# ESP32_with_USBC.net
KiCad netlist of a schematic drawn in Altium Designer
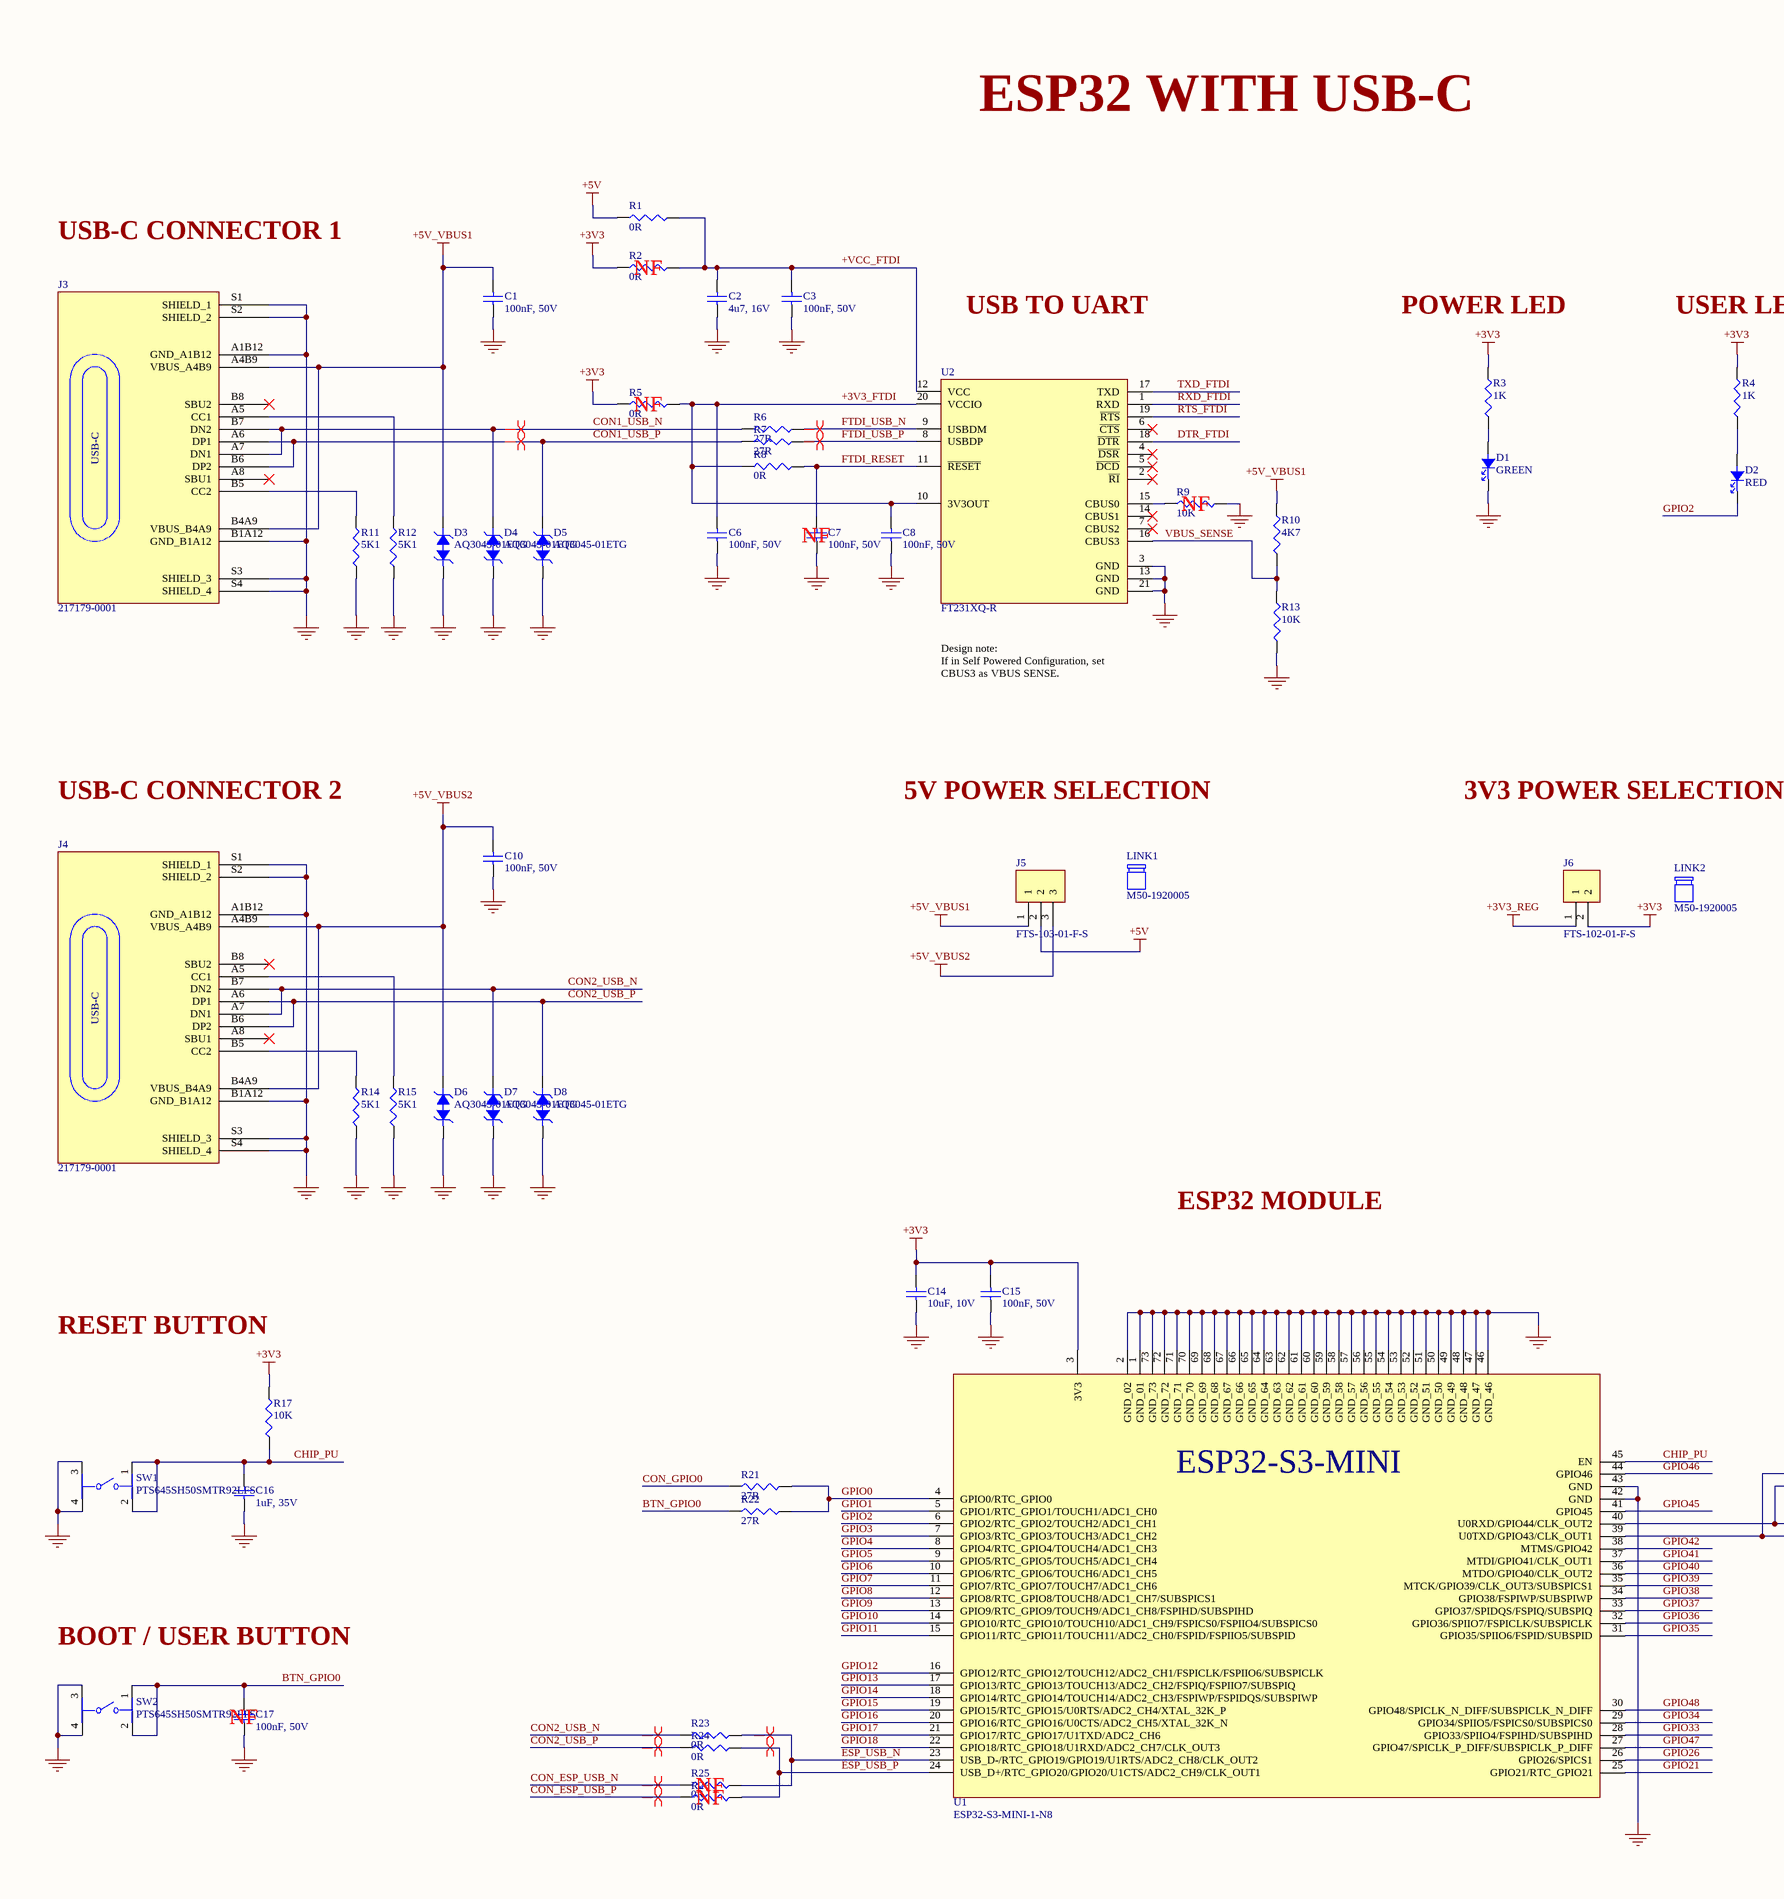
[diagram p0: ESP32 with USBC.SchDoc, left]
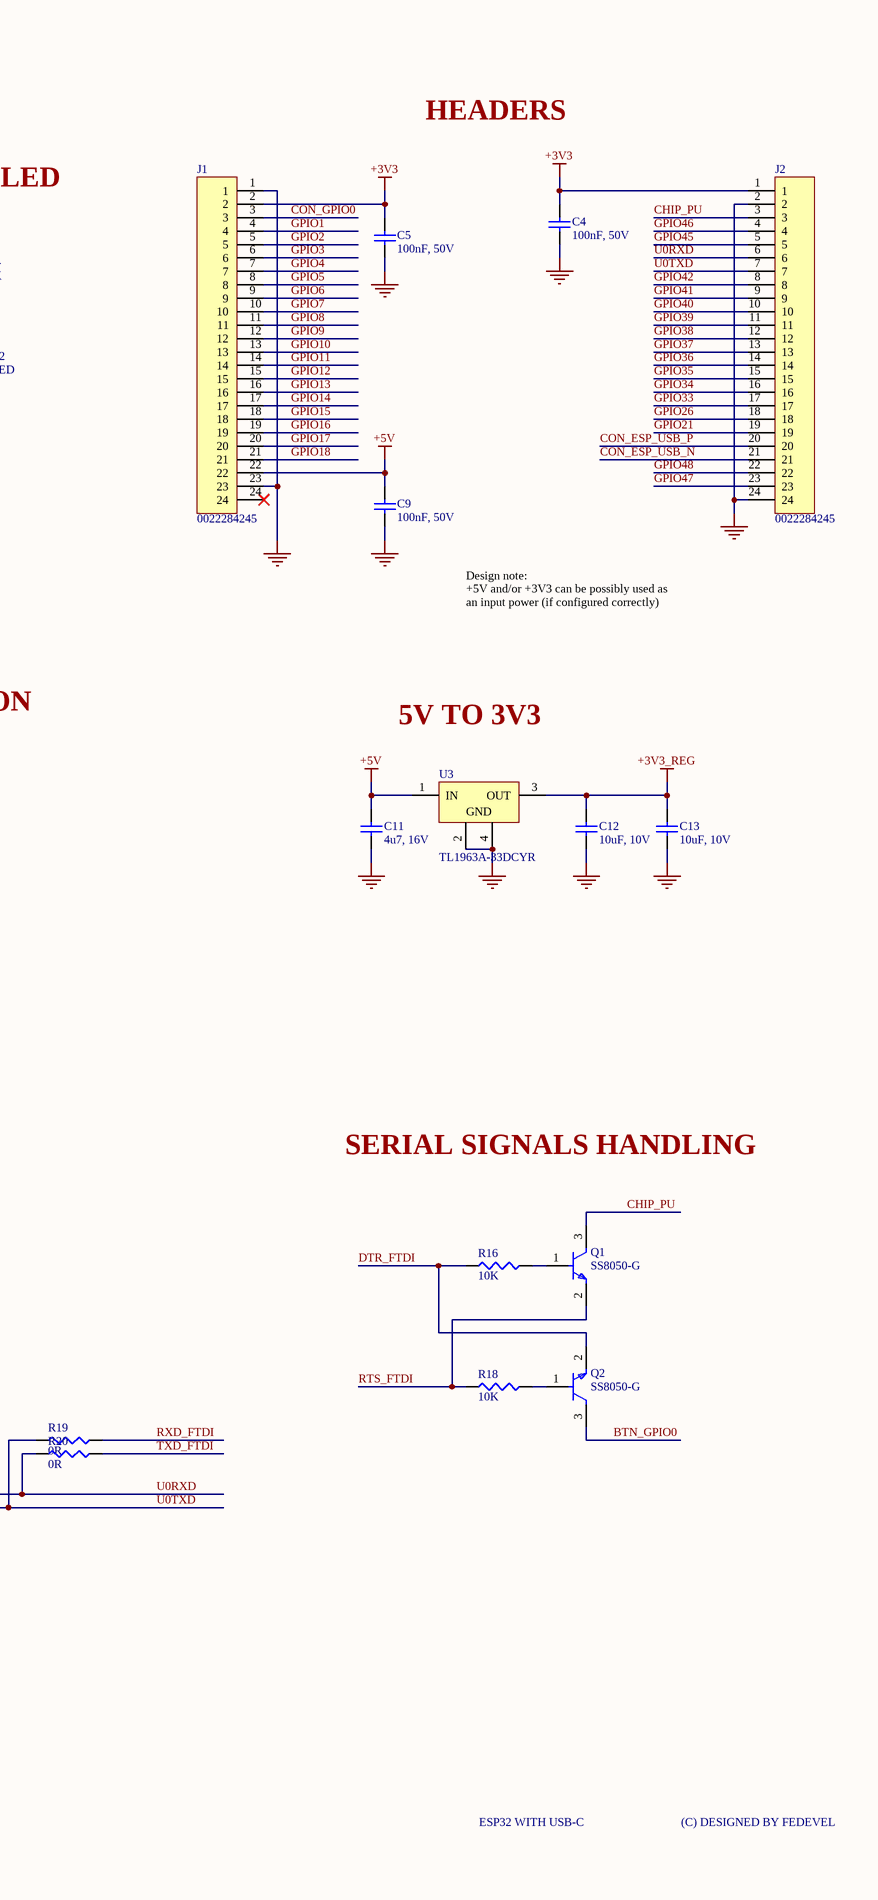
[diagram p1: ESP32 with USBC.SchDoc, right]

(export (version "E")
  (design (tool "Eeschema 10.0.6"))
  (components
    (comp (ref "C1")
      (value "100nF, 50V")
      (footprint "CAPC1005X55N")
      (description "CAP CER 0.1UF 50V X7R 0402")
      (fields
        (field (name "MANUFACTURER") "Samsung")
        (field (name "MANUFACTURER PART NUMBER") "CL05B104KB54PNC")
      )
      (libsource (lib "Schlib") (part "CL05B104KB54PNC"))
    )
    (comp (ref "C2")
      (value "4u7, 16V")
      (footprint "CAPC1005X55N")
      (description "CAP CER 4.7UF 16V X5R 0402")
      (fields
        (field (name "MANUFACTURER") "Samsung")
        (field (name "MANUFACTURER PART NUMBER") "CL05A475MO5NUNC")
      )
      (libsource (lib "Schlib") (part "CL05A475MO5NUNC"))
    )
    (comp (ref "C3")
      (value "100nF, 50V")
      (footprint "CAPC1005X55N")
      (description "CAP CER 0.1UF 50V X7R 0402")
      (fields
        (field (name "MANUFACTURER") "Samsung")
        (field (name "MANUFACTURER PART NUMBER") "CL05B104KB54PNC")
      )
      (libsource (lib "Schlib") (part "CL05B104KB54PNC"))
    )
    (comp (ref "C4")
      (value "100nF, 50V")
      (footprint "CAPC1005X55N")
      (description "CAP CER 0.1UF 50V X7R 0402")
      (fields
        (field (name "MANUFACTURER") "Samsung")
        (field (name "MANUFACTURER PART NUMBER") "CL05B104KB54PNC")
      )
      (libsource (lib "Schlib") (part "CL05B104KB54PNC"))
    )
    (comp (ref "C5")
      (value "100nF, 50V")
      (footprint "CAPC1005X55N")
      (description "CAP CER 0.1UF 50V X7R 0402")
      (fields
        (field (name "MANUFACTURER") "Samsung")
        (field (name "MANUFACTURER PART NUMBER") "CL05B104KB54PNC")
      )
      (libsource (lib "Schlib") (part "CL05B104KB54PNC"))
    )
    (comp (ref "C6")
      (value "100nF, 50V")
      (footprint "CAPC1005X55N")
      (description "CAP CER 0.1UF 50V X7R 0402")
      (fields
        (field (name "MANUFACTURER") "Samsung")
        (field (name "MANUFACTURER PART NUMBER") "CL05B104KB54PNC")
      )
      (libsource (lib "Schlib") (part "CL05B104KB54PNC"))
    )
    (comp (ref "C7")
      (value "100nF, 50V")
      (footprint "CAPC1005X55N")
      (description "CAP CER 0.1UF 50V X7R 0402")
      (fields
        (field (name "MANUFACTURER") "Samsung")
        (field (name "MANUFACTURER PART NUMBER") "CL05B104KB54PNC")
      )
      (libsource (lib "Schlib") (part "CL05B104KB54PNC"))
    )
    (comp (ref "C8")
      (value "100nF, 50V")
      (footprint "CAPC1005X55N")
      (description "CAP CER 0.1UF 50V X7R 0402")
      (fields
        (field (name "MANUFACTURER") "Samsung")
        (field (name "MANUFACTURER PART NUMBER") "CL05B104KB54PNC")
      )
      (libsource (lib "Schlib") (part "CL05B104KB54PNC"))
    )
    (comp (ref "C9")
      (value "100nF, 50V")
      (footprint "CAPC1005X55N")
      (description "CAP CER 0.1UF 50V X7R 0402")
      (fields
        (field (name "MANUFACTURER") "Samsung")
        (field (name "MANUFACTURER PART NUMBER") "CL05B104KB54PNC")
      )
      (libsource (lib "Schlib") (part "CL05B104KB54PNC"))
    )
    (comp (ref "C10")
      (value "100nF, 50V")
      (footprint "CAPC1005X55N")
      (description "CAP CER 0.1UF 50V X7R 0402")
      (fields
        (field (name "MANUFACTURER") "Samsung")
        (field (name "MANUFACTURER PART NUMBER") "CL05B104KB54PNC")
      )
      (libsource (lib "Schlib") (part "CL05B104KB54PNC"))
    )
    (comp (ref "C11")
      (value "4u7, 16V")
      (footprint "CAPC1005X55N")
      (description "CAP CER 4.7UF 16V X5R 0402")
      (fields
        (field (name "MANUFACTURER") "Samsung")
        (field (name "MANUFACTURER PART NUMBER") "CL05A475MO5NUNC")
      )
      (libsource (lib "Schlib") (part "CL05A475MO5NUNC"))
    )
    (comp (ref "C12")
      (value "10uF, 10V")
      (footprint "CAPC1005X55N")
      (description "CAP CER 10UF 10V X5R 0402")
      (fields
        (field (name "MANUFACTURER") "Samsung")
        (field (name "MANUFACTURER PART NUMBER") "CL05A106MP8NUB8")
      )
      (libsource (lib "Schlib") (part "CL05A106MP8NUB8"))
    )
    (comp (ref "C13")
      (value "10uF, 10V")
      (footprint "CAPC1005X55N")
      (description "CAP CER 10UF 10V X5R 0402")
      (fields
        (field (name "MANUFACTURER") "Samsung")
        (field (name "MANUFACTURER PART NUMBER") "CL05A106MP8NUB8")
      )
      (libsource (lib "Schlib") (part "CL05A106MP8NUB8"))
    )
    (comp (ref "C14")
      (value "10uF, 10V")
      (footprint "CAPC1005X55N")
      (description "CAP CER 10UF 10V X5R 0402")
      (fields
        (field (name "MANUFACTURER") "Samsung")
        (field (name "MANUFACTURER PART NUMBER") "CL05A106MP8NUB8")
      )
      (libsource (lib "Schlib") (part "CL05A106MP8NUB8"))
    )
    (comp (ref "C15")
      (value "100nF, 50V")
      (footprint "CAPC1005X55N")
      (description "CAP CER 0.1UF 50V X7R 0402")
      (fields
        (field (name "MANUFACTURER") "Samsung")
        (field (name "MANUFACTURER PART NUMBER") "CL05B104KB54PNC")
      )
      (libsource (lib "Schlib") (part "CL05B104KB54PNC"))
    )
    (comp (ref "C16")
      (value "1uF, 35V")
      (footprint "CAPC1005X55N")
      (description "CAP CER 1UF 35V X5R 0402")
      (fields
        (field (name "MANUFACTURER") "Samsung")
        (field (name "MANUFACTURER PART NUMBER") "CL05A105KL5NRNC")
      )
      (libsource (lib "Schlib") (part "CL05A105KL5NRNC"))
    )
    (comp (ref "C17")
      (value "100nF, 50V")
      (footprint "CAPC1005X55N")
      (description "CAP CER 0.1UF 50V X7R 0402")
      (fields
        (field (name "MANUFACTURER") "Samsung")
        (field (name "MANUFACTURER PART NUMBER") "CL05B104KB54PNC")
      )
      (libsource (lib "Schlib") (part "CL05B104KB54PNC"))
    )
    (comp (ref "D1")
      (value "GREEN")
      (footprint "LED0402G")
      (description "LED YLW-GRN 0402 SMD")
      (fields
        (field (name "MANUFACTURER") "Vishay")
        (field (name "MANUFACTURER PART NUMBER") "VLMG1500-GS08")
      )
      (libsource (lib "Schlib") (part "VLMG1500-GS08"))
    )
    (comp (ref "D2")
      (value "RED")
      (footprint "LED0402R")
      (description "LED RED 0402 SMD")
      (fields
        (field (name "MANUFACTURER") "Vishay")
        (field (name "MANUFACTURER PART NUMBER") "VLMS1500-GS08")
      )
      (libsource (lib "Schlib") (part "VLMS1500-GS08"))
    )
    (comp (ref "D3")
      (value "AQ3045-01ETG")
      (footprint "SOD882")
      (description "TVS DIODE 5.3VWM 12VC SOD882")
      (fields (field (name "MANUFACTURER") "Littelfuse") (field (name "LCSC PART NUMBER") "C3710326"))
      (libsource (lib "Schlib") (part "AQ3045-01ETG"))
    )
    (comp (ref "D4")
      (value "AQ3045-01ETG")
      (footprint "SOD882")
      (description "TVS DIODE 5.3VWM 12VC SOD882")
      (fields (field (name "MANUFACTURER") "Littelfuse") (field (name "LCSC PART NUMBER") "C3710326"))
      (libsource (lib "Schlib") (part "AQ3045-01ETG"))
    )
    (comp (ref "D5")
      (value "AQ3045-01ETG")
      (footprint "SOD882")
      (description "TVS DIODE 5.3VWM 12VC SOD882")
      (fields (field (name "MANUFACTURER") "Littelfuse") (field (name "LCSC PART NUMBER") "C3710326"))
      (libsource (lib "Schlib") (part "AQ3045-01ETG"))
    )
    (comp (ref "D6")
      (value "AQ3045-01ETG")
      (footprint "SOD882")
      (description "TVS DIODE 5.3VWM 12VC SOD882")
      (fields (field (name "MANUFACTURER") "Littelfuse") (field (name "LCSC PART NUMBER") "C3710326"))
      (libsource (lib "Schlib") (part "AQ3045-01ETG"))
    )
    (comp (ref "D7")
      (value "AQ3045-01ETG")
      (footprint "SOD882")
      (description "TVS DIODE 5.3VWM 12VC SOD882")
      (fields (field (name "MANUFACTURER") "Littelfuse") (field (name "LCSC PART NUMBER") "C3710326"))
      (libsource (lib "Schlib") (part "AQ3045-01ETG"))
    )
    (comp (ref "D8")
      (value "AQ3045-01ETG")
      (footprint "SOD882")
      (description "TVS DIODE 5.3VWM 12VC SOD882")
      (fields (field (name "MANUFACTURER") "Littelfuse") (field (name "LCSC PART NUMBER") "C3710326"))
      (libsource (lib "Schlib") (part "AQ3045-01ETG"))
    )
    (comp (ref "J1")
      (value "0022284245")
      (footprint "HDR_1X24_2.54MM")
      (description "CONN HEADER VERT 24POS 2.54MM")
      (fields (field (name "MANUFACTURER") "Molex") (field (name "LCSC PART NUMBER") "C7145888"))
      (libsource (lib "") (part "0022284245_1"))
    )
    (comp (ref "J2")
      (value "0022284245")
      (footprint "HDR_1X24_2.54MM")
      (description "CONN HEADER VERT 24POS 2.54MM")
      (fields (field (name "MANUFACTURER") "Molex") (field (name "LCSC PART NUMBER") "C7145888"))
      (libsource (lib "Schlib") (part "0022284245"))
    )
    (comp (ref "J3")
      (value "217179-0001")
      (footprint "FP-2171790001-MFG")
      (description "CONN RCP USB2.0 TYP C 24P SMD RA")
      (fields (field (name "MANUFACTURER") "Molex") (field (name "LCSC PART NUMBER") "C3197684"))
      (libsource (lib "Schlib") (part "217179-0001"))
    )
    (comp (ref "J4")
      (value "217179-0001")
      (footprint "FP-2171790001-MFG")
      (description "CONN RCP USB2.0 TYP C 24P SMD RA")
      (fields (field (name "MANUFACTURER") "Molex") (field (name "LCSC PART NUMBER") "C3197684"))
      (libsource (lib "Schlib") (part "217179-0001"))
    )
    (comp (ref "J5")
      (value "FTS-103-01-F-S")
      (footprint "HDR_1X3_1.27MM")
      (description "CONN HEADER VERT 3POS 1.27MM")
      (fields (field (name "MANUFACTURER") "Samtec") (field (name "LCSC PART NUMBER") "C3333578"))
      (libsource (lib "Schlib") (part "FTS-103-01-F-S"))
    )
    (comp (ref "J6")
      (value "FTS-102-01-F-S")
      (footprint "HDR_1X2_1.27MM")
      (description "CONN HEADER VERT 2POS 1.27MM")
      (fields (field (name "MANUFACTURER") "Samtec") (field (name "LCSC PART NUMBER") "C6045317"))
      (libsource (lib "Schlib") (part "FTS-102-01-F-S"))
    )
    (comp (ref "LINK1")
      (value "M50-1920005")
      (description "CONN SHUNT 1.27MM RED")
      (fields (field (name "MANUFACTURER") "Harwin") (field (name "LCSC PART NUMBER") "C6985646"))
      (libsource (lib "Schlib") (part "M50-1920005"))
    )
    (comp (ref "LINK2")
      (value "M50-1920005")
      (description "CONN SHUNT 1.27MM RED")
      (fields (field (name "MANUFACTURER") "Harwin") (field (name "LCSC PART NUMBER") "C6985646"))
      (libsource (lib "Schlib") (part "M50-1920005"))
    )
    (comp (ref "Q1")
      (value "SS8050-G")
      (footprint "FP-SS8050-G-IPC_B")
      (description "TRANS NPN 25V 1.5A SOT23-3")
      (fields (field (name "MANUFACTURER") "Comchip") (field (name "LCSC PART NUMBER") "C164886"))
      (libsource (lib "Schlib") (part "SS8050-G"))
    )
    (comp (ref "Q2")
      (value "SS8050-G")
      (footprint "FP-SS8050-G-IPC_B")
      (description "TRANS NPN 25V 1.5A SOT23-3")
      (fields (field (name "MANUFACTURER") "Comchip") (field (name "LCSC PART NUMBER") "C164886"))
      (libsource (lib "Schlib") (part "SS8050-G"))
    )
    (comp (ref "R1")
      (value "0R")
      (footprint "RESC1005X37N")
      (description "RES 0 OHM JUMPER 1/16W 0402")
      (fields
        (field (name "MANUFACTURER") "Yageo")
        (field (name "MANUFACTURER PART NUMBER") "RC0402JR-070RL")
      )
      (libsource (lib "Schlib") (part "RC0402JR-070RL"))
    )
    (comp (ref "R2")
      (value "0R")
      (footprint "RESC1005X37N")
      (description "RES 0 OHM JUMPER 1/16W 0402")
      (fields
        (field (name "MANUFACTURER") "Yageo")
        (field (name "MANUFACTURER PART NUMBER") "RC0402JR-070RL")
      )
      (libsource (lib "Schlib") (part "RC0402JR-070RL"))
    )
    (comp (ref "R3")
      (value "1K")
      (footprint "RESC1005X37N")
      (description "RES 1K OHM 1% 1/16W 0402")
      (fields
        (field (name "MANUFACTURER") "Yageo")
        (field (name "MANUFACTURER PART NUMBER") "RC0402FR-071KL")
      )
      (libsource (lib "Schlib") (part "RC0402FR-071KL"))
    )
    (comp (ref "R4")
      (value "1K")
      (footprint "RESC1005X37N")
      (description "RES 1K OHM 1% 1/16W 0402")
      (fields
        (field (name "MANUFACTURER") "Yageo")
        (field (name "MANUFACTURER PART NUMBER") "RC0402FR-071KL")
      )
      (libsource (lib "Schlib") (part "RC0402FR-071KL"))
    )
    (comp (ref "R5")
      (value "0R")
      (footprint "RESC1005X37N")
      (description "RES 0 OHM JUMPER 1/16W 0402")
      (fields
        (field (name "MANUFACTURER") "Yageo")
        (field (name "MANUFACTURER PART NUMBER") "RC0402JR-070RL")
      )
      (libsource (lib "Schlib") (part "RC0402JR-070RL"))
    )
    (comp (ref "R6")
      (value "27R")
      (footprint "RESC1005X37N")
      (description "RES 27 OHM 1% 1/16W 0402")
      (fields
        (field (name "MANUFACTURER") "Yageo")
        (field (name "MANUFACTURER PART NUMBER") "RC0402FR-0727RL")
      )
      (libsource (lib "Schlib") (part "RC0402FR-0727RL"))
    )
    (comp (ref "R7")
      (value "27R")
      (footprint "RESC1005X37N")
      (description "RES 27 OHM 1% 1/16W 0402")
      (fields
        (field (name "MANUFACTURER") "Yageo")
        (field (name "MANUFACTURER PART NUMBER") "RC0402FR-0727RL")
      )
      (libsource (lib "Schlib") (part "RC0402FR-0727RL"))
    )
    (comp (ref "R8")
      (value "0R")
      (footprint "RESC1005X37N")
      (description "RES 0 OHM JUMPER 1/16W 0402")
      (fields
        (field (name "MANUFACTURER") "Yageo")
        (field (name "MANUFACTURER PART NUMBER") "RC0402JR-070RL")
      )
      (libsource (lib "Schlib") (part "RC0402JR-070RL"))
    )
    (comp (ref "R9")
      (value "10K")
      (footprint "RESC1005X37N")
      (description "RES SMD 10K OHM 1% 1/16W 0402")
      (fields
        (field (name "MANUFACTURER") "Yageo")
        (field (name "MANUFACTURER PART NUMBER") "AC0402FR-0710KL")
      )
      (libsource (lib "Schlib") (part "AC0402FR-0710KL"))
    )
    (comp (ref "R10")
      (value "4K7")
      (footprint "RESC1005X37N")
      (description "RES 4.7K OHM 1% 1/16W 0402")
      (fields
        (field (name "MANUFACTURER") "Yageo")
        (field (name "MANUFACTURER PART NUMBER") "RC0402FR-074K7L")
      )
      (libsource (lib "Schlib") (part "RC0402FR-074K7L"))
    )
    (comp (ref "R11")
      (value "5K1")
      (footprint "RESC1005X37N")
      (description "RES SMD 5.1K OHM 1% 1/16W 0402")
      (fields
        (field (name "MANUFACTURER") "Yageo")
        (field (name "MANUFACTURER PART NUMBER") "AC0402FR-075K1L")
      )
      (libsource (lib "Schlib") (part "AC0402FR-075K1L"))
    )
    (comp (ref "R12")
      (value "5K1")
      (footprint "RESC1005X37N")
      (description "RES SMD 5.1K OHM 1% 1/16W 0402")
      (fields
        (field (name "MANUFACTURER") "Yageo")
        (field (name "MANUFACTURER PART NUMBER") "AC0402FR-075K1L")
      )
      (libsource (lib "Schlib") (part "AC0402FR-075K1L"))
    )
    (comp (ref "R13")
      (value "10K")
      (footprint "RESC1005X37N")
      (description "RES SMD 10K OHM 1% 1/16W 0402")
      (fields
        (field (name "MANUFACTURER") "Yageo")
        (field (name "MANUFACTURER PART NUMBER") "AC0402FR-0710KL")
      )
      (libsource (lib "Schlib") (part "AC0402FR-0710KL"))
    )
    (comp (ref "R14")
      (value "5K1")
      (footprint "RESC1005X37N")
      (description "RES SMD 5.1K OHM 1% 1/16W 0402")
      (fields
        (field (name "MANUFACTURER") "Yageo")
        (field (name "MANUFACTURER PART NUMBER") "AC0402FR-075K1L")
      )
      (libsource (lib "Schlib") (part "AC0402FR-075K1L"))
    )
    (comp (ref "R15")
      (value "5K1")
      (footprint "RESC1005X37N")
      (description "RES SMD 5.1K OHM 1% 1/16W 0402")
      (fields
        (field (name "MANUFACTURER") "Yageo")
        (field (name "MANUFACTURER PART NUMBER") "AC0402FR-075K1L")
      )
      (libsource (lib "Schlib") (part "AC0402FR-075K1L"))
    )
    (comp (ref "R16")
      (value "10K")
      (footprint "RESC1005X37N")
      (description "RES SMD 10K OHM 1% 1/16W 0402")
      (fields
        (field (name "MANUFACTURER") "Yageo")
        (field (name "MANUFACTURER PART NUMBER") "AC0402FR-0710KL")
      )
      (libsource (lib "Schlib") (part "AC0402FR-0710KL"))
    )
    (comp (ref "R17")
      (value "10K")
      (footprint "RESC1005X37N")
      (description "RES SMD 10K OHM 1% 1/16W 0402")
      (fields
        (field (name "MANUFACTURER") "Yageo")
        (field (name "MANUFACTURER PART NUMBER") "AC0402FR-0710KL")
      )
      (libsource (lib "Schlib") (part "AC0402FR-0710KL"))
    )
    (comp (ref "R18")
      (value "10K")
      (footprint "RESC1005X37N")
      (description "RES SMD 10K OHM 1% 1/16W 0402")
      (fields
        (field (name "MANUFACTURER") "Yageo")
        (field (name "MANUFACTURER PART NUMBER") "AC0402FR-0710KL")
      )
      (libsource (lib "Schlib") (part "AC0402FR-0710KL"))
    )
    (comp (ref "R19")
      (value "0R")
      (footprint "RESC1005X37N")
      (description "RES 0 OHM JUMPER 1/16W 0402")
      (fields
        (field (name "MANUFACTURER") "Yageo")
        (field (name "MANUFACTURER PART NUMBER") "RC0402JR-070RL")
      )
      (libsource (lib "Schlib") (part "RC0402JR-070RL"))
    )
    (comp (ref "R20")
      (value "0R")
      (footprint "RESC1005X37N")
      (description "RES 0 OHM JUMPER 1/16W 0402")
      (fields
        (field (name "MANUFACTURER") "Yageo")
        (field (name "MANUFACTURER PART NUMBER") "RC0402JR-070RL")
      )
      (libsource (lib "Schlib") (part "RC0402JR-070RL"))
    )
    (comp (ref "R21")
      (value "27R")
      (footprint "RESC1005X37N")
      (description "RES 27 OHM 1% 1/16W 0402")
      (fields
        (field (name "MANUFACTURER") "Yageo")
        (field (name "MANUFACTURER PART NUMBER") "RC0402FR-0727RL")
      )
      (libsource (lib "Schlib") (part "RC0402FR-0727RL"))
    )
    (comp (ref "R22")
      (value "27R")
      (footprint "RESC1005X37N")
      (description "RES 27 OHM 1% 1/16W 0402")
      (fields
        (field (name "MANUFACTURER") "Yageo")
        (field (name "MANUFACTURER PART NUMBER") "RC0402FR-0727RL")
      )
      (libsource (lib "Schlib") (part "RC0402FR-0727RL"))
    )
    (comp (ref "R23")
      (value "0R")
      (footprint "RESC1005X37N")
      (description "RES 0 OHM JUMPER 1/16W 0402")
      (fields
        (field (name "MANUFACTURER") "Yageo")
        (field (name "MANUFACTURER PART NUMBER") "RC0402JR-070RL")
      )
      (libsource (lib "Schlib") (part "RC0402JR-070RL"))
    )
    (comp (ref "R24")
      (value "0R")
      (footprint "RESC1005X37N")
      (description "RES 0 OHM JUMPER 1/16W 0402")
      (fields
        (field (name "MANUFACTURER") "Yageo")
        (field (name "MANUFACTURER PART NUMBER") "RC0402JR-070RL")
      )
      (libsource (lib "Schlib") (part "RC0402JR-070RL"))
    )
    (comp (ref "R25")
      (value "0R")
      (footprint "RESC1005X37N")
      (description "RES 0 OHM JUMPER 1/16W 0402")
      (fields
        (field (name "MANUFACTURER") "Yageo")
        (field (name "MANUFACTURER PART NUMBER") "RC0402JR-070RL")
      )
      (libsource (lib "Schlib") (part "RC0402JR-070RL"))
    )
    (comp (ref "R26")
      (value "0R")
      (footprint "RESC1005X37N")
      (description "RES 0 OHM JUMPER 1/16W 0402")
      (fields
        (field (name "MANUFACTURER") "Yageo")
        (field (name "MANUFACTURER PART NUMBER") "RC0402JR-070RL")
      )
      (libsource (lib "Schlib") (part "RC0402JR-070RL"))
    )
    (comp (ref "SW1")
      (value "PTS645SH50SMTR92LFS")
      (footprint "FP-PTS645SH50SMTR92LFS-MFG")
      (description "SWITCH TACTILE SPST-NO 0.05A 12V")
      (fields (field (name "MANUFACTURER") "ITT C&K") (field (name "LCSC PART NUMBER") "C221869"))
      (libsource (lib "Schlib") (part "PTS645SH50SMTR92LFS"))
    )
    (comp (ref "SW2")
      (value "PTS645SH50SMTR92LFS")
      (footprint "FP-PTS645SH50SMTR92LFS-MFG")
      (description "SWITCH TACTILE SPST-NO 0.05A 12V")
      (fields (field (name "MANUFACTURER") "ITT C&K") (field (name "LCSC PART NUMBER") "C221869"))
      (libsource (lib "Schlib") (part "PTS645SH50SMTR92LFS"))
    )
    (comp (ref "U1")
      (value "ESP32-S3-MINI-1-N8")
      (footprint "XCVR_ESP32-S3-MINI-1-N8")
      (description "SMD Module, ESP32-S3FN8, 8 mb Sp")
      (fields (field (name "MANUFACTURER") "Espressif Systems") (field (name "LCSC PART NUMBER") "C2913206"))
      (libsource (lib "Schlib") (part "ESP32-S3-MINI-1-N8"))
    )
    (comp (ref "U2")
      (value "FT231XQ-R")
      (footprint "FP-QFN-20-IPC_B")
      (description "IC USB SERIAL FULL UART 20QFN")
      (fields (field (name "MANUFACTURER") "FTDI") (field (name "LCSC PART NUMBER") "C132159"))
      (libsource (lib "Schlib") (part "FT231XQ-R"))
    )
    (comp (ref "U3")
      (value "TL1963A-33DCYR")
      (footprint "DCY0004A_N")
      (description "IC REG LINEAR 3.3V 1.5A SOT223-4")
      (fields (field (name "MANUFACTURER") "Texas Instruments") (field (name "LCSC PART NUMBER") "C181262"))
      (libsource (lib "Schlib") (part "TL1963A-33DCYR"))
    )
  )
  (nets
    (net (code "1") (name "+3V3") (class "Default")
      (node (ref "C14") (pin "2") (pinfunction "2_2") (pintype "passive"))
      (node (ref "C15") (pin "2") (pinfunction "2_2") (pintype "passive"))
      (node (ref "C4") (pin "2") (pinfunction "2_2") (pintype "passive"))
      (node (ref "C5") (pin "2") (pinfunction "2_2") (pintype "passive"))
      (node (ref "J1") (pin "2") (pinfunction "2_2") (pintype "passive"))
      (node (ref "J2") (pin "1") (pinfunction "1_1") (pintype "passive"))
      (node (ref "J6") (pin "2") (pinfunction "2_2") (pintype "passive"))
      (node (ref "R17") (pin "2") (pinfunction "2_2") (pintype "passive"))
      (node (ref "R2") (pin "1") (pinfunction "1_1") (pintype "passive"))
      (node (ref "R3") (pin "2") (pinfunction "2_2") (pintype "passive"))
      (node (ref "R4") (pin "2") (pinfunction "2_2") (pintype "passive"))
      (node (ref "R5") (pin "1") (pinfunction "1_1") (pintype "passive"))
      (node (ref "U1") (pin "3") (pinfunction "3V3_3") (pintype "passive"))
    )
    (net (code "2") (name "+3V3_REG") (class "Default")
      (node (ref "C12") (pin "2") (pinfunction "2_2") (pintype "passive"))
      (node (ref "C13") (pin "2") (pinfunction "2_2") (pintype "passive"))
      (node (ref "J6") (pin "1") (pinfunction "1_1") (pintype "passive"))
      (node (ref "U3") (pin "3") (pinfunction "OUT_3") (pintype "power_in"))
    )
    (net (code "3") (name "+5V") (class "Default")
      (node (ref "C11") (pin "2") (pinfunction "2_2") (pintype "passive"))
      (node (ref "C9") (pin "2") (pinfunction "2_2") (pintype "passive"))
      (node (ref "J1") (pin "22") (pinfunction "22_22") (pintype "passive"))
      (node (ref "J5") (pin "2") (pinfunction "2_2") (pintype "passive"))
      (node (ref "R1") (pin "1") (pinfunction "1_1") (pintype "passive"))
      (node (ref "U3") (pin "1") (pinfunction "IN_1") (pintype "power_in"))
    )
    (net (code "4") (name "+5V_VBUS1") (class "Default")
      (node (ref "C1") (pin "2") (pinfunction "2_2") (pintype "passive"))
      (node (ref "D3") (pin "2") (pinfunction "2_2") (pintype "passive"))
      (node (ref "J3") (pin "A4B9") (pinfunction "VBUS_A4B9_A4B9") (pintype "passive"))
      (node (ref "J3") (pin "B4A9") (pinfunction "VBUS_B4A9_B4A9") (pintype "passive"))
      (node (ref "J5") (pin "1") (pinfunction "1_1") (pintype "passive"))
      (node (ref "R10") (pin "2") (pinfunction "2_2") (pintype "passive"))
    )
    (net (code "5") (name "+5V_VBUS2") (class "Default")
      (node (ref "C10") (pin "2") (pinfunction "2_2") (pintype "passive"))
      (node (ref "D6") (pin "2") (pinfunction "2_2") (pintype "passive"))
      (node (ref "J4") (pin "A4B9") (pinfunction "VBUS_A4B9_A4B9") (pintype "passive"))
      (node (ref "J4") (pin "B4A9") (pinfunction "VBUS_B4A9_B4A9") (pintype "passive"))
      (node (ref "J5") (pin "3") (pinfunction "3_3") (pintype "passive"))
    )
    (net (code "6") (name "/+3V3_FTDI") (class "Default")
      (node (ref "C6") (pin "2") (pinfunction "2_2") (pintype "passive"))
      (node (ref "C8") (pin "2") (pinfunction "2_2") (pintype "passive"))
      (node (ref "R5") (pin "2") (pinfunction "2_2") (pintype "passive"))
      (node (ref "R8") (pin "1") (pinfunction "1_1") (pintype "passive"))
      (node (ref "U2") (pin "10") (pinfunction "3V3OUT_10") (pintype "passive"))
      (node (ref "U2") (pin "20") (pinfunction "VCCIO_20") (pintype "passive"))
    )
    (net (code "7") (name "/+VCC_FTDI") (class "Default")
      (node (ref "C2") (pin "2") (pinfunction "2_2") (pintype "passive"))
      (node (ref "C3") (pin "2") (pinfunction "2_2") (pintype "passive"))
      (node (ref "R1") (pin "2") (pinfunction "2_2") (pintype "passive"))
      (node (ref "R2") (pin "2") (pinfunction "2_2") (pintype "passive"))
      (node (ref "U2") (pin "12") (pinfunction "VCC_12") (pintype "passive"))
    )
    (net (code "8") (name "/BTN_GPIO0") (class "Default")
      (node (ref "C17") (pin "2") (pinfunction "2_2") (pintype "passive"))
      (node (ref "Q2") (pin "3") (pinfunction "C_3") (pintype "passive"))
      (node (ref "R22") (pin "1") (pinfunction "1_1") (pintype "passive"))
      (node (ref "SW2") (pin "1") (pinfunction "1_1") (pintype "passive"))
      (node (ref "SW2") (pin "2") (pinfunction "2_2") (pintype "passive"))
    )
    (net (code "9") (name "/CHIP_PU") (class "Default")
      (node (ref "C16") (pin "2") (pinfunction "2_2") (pintype "passive"))
      (node (ref "J2") (pin "3") (pinfunction "3_3") (pintype "passive"))
      (node (ref "Q1") (pin "3") (pinfunction "C_3") (pintype "passive"))
      (node (ref "R17") (pin "1") (pinfunction "1_1") (pintype "passive"))
      (node (ref "SW1") (pin "1") (pinfunction "1_1") (pintype "passive"))
      (node (ref "SW1") (pin "2") (pinfunction "2_2") (pintype "passive"))
      (node (ref "U1") (pin "45") (pinfunction "EN_45") (pintype "passive"))
    )
    (net (code "10") (name "/CON1_USB_N") (class "Default")
      (node (ref "D4") (pin "2") (pinfunction "2_2") (pintype "passive"))
      (node (ref "J3") (pin "A7") (pinfunction "DN1_A7") (pintype "passive"))
      (node (ref "J3") (pin "B7") (pinfunction "DN2_B7") (pintype "passive"))
      (node (ref "R6") (pin "1") (pinfunction "1_1") (pintype "passive"))
    )
    (net (code "11") (name "/CON1_USB_P") (class "Default")
      (node (ref "D5") (pin "2") (pinfunction "2_2") (pintype "passive"))
      (node (ref "J3") (pin "A6") (pinfunction "DP1_A6") (pintype "passive"))
      (node (ref "J3") (pin "B6") (pinfunction "DP2_B6") (pintype "passive"))
      (node (ref "R7") (pin "1") (pinfunction "1_1") (pintype "passive"))
    )
    (net (code "12") (name "/CON2_USB_N") (class "Default")
      (node (ref "D7") (pin "2") (pinfunction "2_2") (pintype "passive"))
      (node (ref "J4") (pin "A7") (pinfunction "DN1_A7") (pintype "passive"))
      (node (ref "J4") (pin "B7") (pinfunction "DN2_B7") (pintype "passive"))
      (node (ref "R23") (pin "1") (pinfunction "1_1") (pintype "passive"))
    )
    (net (code "13") (name "/CON2_USB_P") (class "Default")
      (node (ref "D8") (pin "2") (pinfunction "2_2") (pintype "passive"))
      (node (ref "J4") (pin "A6") (pinfunction "DP1_A6") (pintype "passive"))
      (node (ref "J4") (pin "B6") (pinfunction "DP2_B6") (pintype "passive"))
      (node (ref "R24") (pin "1") (pinfunction "1_1") (pintype "passive"))
    )
    (net (code "14") (name "/CON_ESP_USB_N") (class "Default")
      (node (ref "J2") (pin "21") (pinfunction "21_21") (pintype "passive"))
      (node (ref "R25") (pin "1") (pinfunction "1_1") (pintype "passive"))
    )
    (net (code "15") (name "/CON_ESP_USB_P") (class "Default")
      (node (ref "J2") (pin "20") (pinfunction "20_20") (pintype "passive"))
      (node (ref "R26") (pin "1") (pinfunction "1_1") (pintype "passive"))
    )
    (net (code "16") (name "/CON_GPIO0") (class "Default")
      (node (ref "J1") (pin "3") (pinfunction "3_3") (pintype "passive"))
      (node (ref "R21") (pin "1") (pinfunction "1_1") (pintype "passive"))
    )
    (net (code "17") (name "/DTR_FTDI") (class "Default")
      (node (ref "Q2") (pin "2") (pinfunction "E_2") (pintype "passive"))
      (node (ref "R16") (pin "1") (pinfunction "1_1") (pintype "passive"))
      (node (ref "U2") (pin "18") (pinfunction "~{DTR}_18") (pintype "passive"))
    )
    (net (code "18") (name "/ESP_USB_N") (class "Default")
      (node (ref "R23") (pin "2") (pinfunction "2_2") (pintype "passive"))
      (node (ref "R25") (pin "2") (pinfunction "2_2") (pintype "passive"))
      (node (ref "U1") (pin "23") (pinfunction "USB_D-/RTC_GPIO19/GPIO19/U1RTS/ADC2_CH8/CLK_OUT2_23") (pintype "passive"))
    )
    (net (code "19") (name "/ESP_USB_P") (class "Default")
      (node (ref "R24") (pin "2") (pinfunction "2_2") (pintype "passive"))
      (node (ref "R26") (pin "2") (pinfunction "2_2") (pintype "passive"))
      (node (ref "U1") (pin "24") (pinfunction "USB_D+/RTC_GPIO20/GPIO20/U1CTS/ADC2_CH9/CLK_OUT1_24") (pintype "passive"))
    )
    (net (code "20") (name "/FTDI_RESET") (class "Default")
      (node (ref "C7") (pin "2") (pinfunction "2_2") (pintype "passive"))
      (node (ref "R8") (pin "2") (pinfunction "2_2") (pintype "passive"))
      (node (ref "U2") (pin "11") (pinfunction "~{RESET}_11") (pintype "passive"))
    )
    (net (code "21") (name "/FTDI_USB_N") (class "Default")
      (node (ref "R6") (pin "2") (pinfunction "2_2") (pintype "passive"))
      (node (ref "U2") (pin "9") (pinfunction "USBDM_9") (pintype "passive"))
    )
    (net (code "22") (name "/FTDI_USB_P") (class "Default")
      (node (ref "R7") (pin "2") (pinfunction "2_2") (pintype "passive"))
      (node (ref "U2") (pin "8") (pinfunction "USBDP_8") (pintype "passive"))
    )
    (net (code "23") (name "/GPIO0") (class "Default")
      (node (ref "R21") (pin "2") (pinfunction "2_2") (pintype "passive"))
      (node (ref "R22") (pin "2") (pinfunction "2_2") (pintype "passive"))
      (node (ref "U1") (pin "4") (pinfunction "GPIO0/RTC_GPIO0_4") (pintype "passive"))
    )
    (net (code "24") (name "/GPIO1") (class "Default")
      (node (ref "J1") (pin "4") (pinfunction "4_4") (pintype "passive"))
      (node (ref "U1") (pin "5") (pinfunction "GPIO1/RTC_GPIO1/TOUCH1/ADC1_CH0_5") (pintype "passive"))
    )
    (net (code "25") (name "/GPIO2") (class "Default")
      (node (ref "D2") (pin "1") (pinfunction "1_1") (pintype "passive"))
      (node (ref "J1") (pin "5") (pinfunction "5_5") (pintype "passive"))
      (node (ref "U1") (pin "6") (pinfunction "GPIO2/RTC_GPIO2/TOUCH2/ADC1_CH1_6") (pintype "passive"))
    )
    (net (code "26") (name "/GPIO3") (class "Default")
      (node (ref "J1") (pin "6") (pinfunction "6_6") (pintype "passive"))
      (node (ref "U1") (pin "7") (pinfunction "GPIO3/RTC_GPIO3/TOUCH3/ADC1_CH2_7") (pintype "passive"))
    )
    (net (code "27") (name "/GPIO4") (class "Default")
      (node (ref "J1") (pin "7") (pinfunction "7_7") (pintype "passive"))
      (node (ref "U1") (pin "8") (pinfunction "GPIO4/RTC_GPIO4/TOUCH4/ADC1_CH3_8") (pintype "passive"))
    )
    (net (code "28") (name "/GPIO5") (class "Default")
      (node (ref "J1") (pin "8") (pinfunction "8_8") (pintype "passive"))
      (node (ref "U1") (pin "9") (pinfunction "GPIO5/RTC_GPIO5/TOUCH5/ADC1_CH4_9") (pintype "passive"))
    )
    (net (code "29") (name "/GPIO6") (class "Default")
      (node (ref "J1") (pin "9") (pinfunction "9_9") (pintype "passive"))
      (node (ref "U1") (pin "10") (pinfunction "GPIO6/RTC_GPIO6/TOUCH6/ADC1_CH5_10") (pintype "passive"))
    )
    (net (code "30") (name "/GPIO7") (class "Default")
      (node (ref "J1") (pin "10") (pinfunction "10_10") (pintype "passive"))
      (node (ref "U1") (pin "11") (pinfunction "GPIO7/RTC_GPIO7/TOUCH7/ADC1_CH6_11") (pintype "passive"))
    )
    (net (code "31") (name "/GPIO8") (class "Default")
      (node (ref "J1") (pin "11") (pinfunction "11_11") (pintype "passive"))
      (node (ref "U1") (pin "12") (pinfunction "GPIO8/RTC_GPIO8/TOUCH8/ADC1_CH7/SUBSPICS1_12") (pintype "passive"))
    )
    (net (code "32") (name "/GPIO9") (class "Default")
      (node (ref "J1") (pin "12") (pinfunction "12_12") (pintype "passive"))
      (node (ref "U1") (pin "13") (pinfunction "GPIO9/RTC_GPIO9/TOUCH9/ADC1_CH8/FSPIHD/SUBSPIHD_13") (pintype "passive"))
    )
    (net (code "33") (name "/GPIO10") (class "Default")
      (node (ref "J1") (pin "13") (pinfunction "13_13") (pintype "passive"))
      (node (ref "U1") (pin "14") (pinfunction "GPIO10/RTC_GPIO10/TOUCH10/ADC1_CH9/FSPICS0/FSPIIO4/SUBSPICS0_14") (pintype "passive"))
    )
    (net (code "34") (name "/GPIO11") (class "Default")
      (node (ref "J1") (pin "14") (pinfunction "14_14") (pintype "passive"))
      (node (ref "U1") (pin "15") (pinfunction "GPIO11/RTC_GPIO11/TOUCH11/ADC2_CH0/FSPID/FSPIIO5/SUBSPID_15") (pintype "passive"))
    )
    (net (code "35") (name "/GPIO12") (class "Default")
      (node (ref "J1") (pin "15") (pinfunction "15_15") (pintype "passive"))
      (node (ref "U1") (pin "16") (pinfunction "GPIO12/RTC_GPIO12/TOUCH12/ADC2_CH1/FSPICLK/FSPIIO6/SUBSPICLK_16") (pintype "passive"))
    )
    (net (code "36") (name "/GPIO13") (class "Default")
      (node (ref "J1") (pin "16") (pinfunction "16_16") (pintype "passive"))
      (node (ref "U1") (pin "17") (pinfunction "GPIO13/RTC_GPIO13/TOUCH13/ADC2_CH2/FSPIQ/FSPIIO7/SUBSPIQ_17") (pintype "passive"))
    )
    (net (code "37") (name "/GPIO14") (class "Default")
      (node (ref "J1") (pin "17") (pinfunction "17_17") (pintype "passive"))
      (node (ref "U1") (pin "18") (pinfunction "GPIO14/RTC_GPIO14/TOUCH14/ADC2_CH3/FSPIWP/FSPIDQS/SUBSPIWP_18") (pintype "passive"))
    )
    (net (code "38") (name "/GPIO15") (class "Default")
      (node (ref "J1") (pin "18") (pinfunction "18_18") (pintype "passive"))
      (node (ref "U1") (pin "19") (pinfunction "GPIO15/RTC_GPIO15/U0RTS/ADC2_CH4/XTAL_32K_P_19") (pintype "passive"))
    )
    (net (code "39") (name "/GPIO16") (class "Default")
      (node (ref "J1") (pin "19") (pinfunction "19_19") (pintype "passive"))
      (node (ref "U1") (pin "20") (pinfunction "GPIO16/RTC_GPIO16/U0CTS/ADC2_CH5/XTAL_32K_N_20") (pintype "passive"))
    )
    (net (code "40") (name "/GPIO17") (class "Default")
      (node (ref "J1") (pin "20") (pinfunction "20_20") (pintype "passive"))
      (node (ref "U1") (pin "21") (pinfunction "GPIO17/RTC_GPIO17/U1TXD/ADC2_CH6_21") (pintype "passive"))
    )
    (net (code "41") (name "/GPIO18") (class "Default")
      (node (ref "J1") (pin "21") (pinfunction "21_21") (pintype "passive"))
      (node (ref "U1") (pin "22") (pinfunction "GPIO18/RTC_GPIO18/U1RXD/ADC2_CH7/CLK_OUT3_22") (pintype "passive"))
    )
    (net (code "42") (name "/GPIO21") (class "Default")
      (node (ref "J2") (pin "19") (pinfunction "19_19") (pintype "passive"))
      (node (ref "U1") (pin "25") (pinfunction "GPIO21/RTC_GPIO21_25") (pintype "passive"))
    )
    (net (code "43") (name "/GPIO26") (class "Default")
      (node (ref "J2") (pin "18") (pinfunction "18_18") (pintype "passive"))
      (node (ref "U1") (pin "26") (pinfunction "GPIO26/SPICS1_26") (pintype "passive"))
    )
    (net (code "44") (name "/GPIO33") (class "Default")
      (node (ref "J2") (pin "17") (pinfunction "17_17") (pintype "passive"))
      (node (ref "U1") (pin "28") (pinfunction "GPIO33/SPIIO4/FSPIHD/SUBSPIHD_28") (pintype "passive"))
    )
    (net (code "45") (name "/GPIO34") (class "Default")
      (node (ref "J2") (pin "16") (pinfunction "16_16") (pintype "passive"))
      (node (ref "U1") (pin "29") (pinfunction "GPIO34/SPIIO5/FSPICS0/SUBSPICS0_29") (pintype "passive"))
    )
    (net (code "46") (name "/GPIO35") (class "Default")
      (node (ref "J2") (pin "15") (pinfunction "15_15") (pintype "passive"))
      (node (ref "U1") (pin "31") (pinfunction "GPIO35/SPIIO6/FSPID/SUBSPID_31") (pintype "passive"))
    )
    (net (code "47") (name "/GPIO36") (class "Default")
      (node (ref "J2") (pin "14") (pinfunction "14_14") (pintype "passive"))
      (node (ref "U1") (pin "32") (pinfunction "GPIO36/SPIIO7/FSPICLK/SUBSPICLK_32") (pintype "passive"))
    )
    (net (code "48") (name "/GPIO37") (class "Default")
      (node (ref "J2") (pin "13") (pinfunction "13_13") (pintype "passive"))
      (node (ref "U1") (pin "33") (pinfunction "GPIO37/SPIDQS/FSPIQ/SUBSPIQ_33") (pintype "passive"))
    )
    (net (code "49") (name "/GPIO38") (class "Default")
      (node (ref "J2") (pin "12") (pinfunction "12_12") (pintype "passive"))
      (node (ref "U1") (pin "34") (pinfunction "GPIO38/FSPIWP/SUBSPIWP_34") (pintype "passive"))
    )
    (net (code "50") (name "/GPIO39") (class "Default")
      (node (ref "J2") (pin "11") (pinfunction "11_11") (pintype "passive"))
      (node (ref "U1") (pin "35") (pinfunction "MTCK/GPIO39/CLK_OUT3/SUBSPICS1_35") (pintype "passive"))
    )
    (net (code "51") (name "/GPIO40") (class "Default")
      (node (ref "J2") (pin "10") (pinfunction "10_10") (pintype "passive"))
      (node (ref "U1") (pin "36") (pinfunction "MTDO/GPIO40/CLK_OUT2_36") (pintype "passive"))
    )
    (net (code "52") (name "/GPIO41") (class "Default")
      (node (ref "J2") (pin "9") (pinfunction "9_9") (pintype "passive"))
      (node (ref "U1") (pin "37") (pinfunction "MTDI/GPIO41/CLK_OUT1_37") (pintype "passive"))
    )
    (net (code "53") (name "/GPIO42") (class "Default")
      (node (ref "J2") (pin "8") (pinfunction "8_8") (pintype "passive"))
      (node (ref "U1") (pin "38") (pinfunction "MTMS/GPIO42_38") (pintype "passive"))
    )
    (net (code "54") (name "/GPIO45") (class "Default")
      (node (ref "J2") (pin "5") (pinfunction "5_5") (pintype "passive"))
      (node (ref "U1") (pin "41") (pinfunction "GPIO45_41") (pintype "passive"))
    )
    (net (code "55") (name "/GPIO46") (class "Default")
      (node (ref "J2") (pin "4") (pinfunction "4_4") (pintype "passive"))
      (node (ref "U1") (pin "44") (pinfunction "GPIO46_44") (pintype "passive"))
    )
    (net (code "56") (name "/GPIO47") (class "Default")
      (node (ref "J2") (pin "23") (pinfunction "23_23") (pintype "passive"))
      (node (ref "U1") (pin "27") (pinfunction "GPIO47/SPICLK_P_DIFF/SUBSPICLK_P_DIFF_27") (pintype "passive"))
    )
    (net (code "57") (name "/GPIO48") (class "Default")
      (node (ref "J2") (pin "22") (pinfunction "22_22") (pintype "passive"))
      (node (ref "U1") (pin "30") (pinfunction "GPIO48/SPICLK_N_DIFF/SUBSPICLK_N_DIFF_30") (pintype "passive"))
    )
    (net (code "58") (name "/RTS_FTDI") (class "Default")
      (node (ref "Q1") (pin "2") (pinfunction "E_2") (pintype "passive"))
      (node (ref "R18") (pin "1") (pinfunction "1_1") (pintype "passive"))
      (node (ref "U2") (pin "19") (pinfunction "~{RTS}_19") (pintype "passive"))
    )
    (net (code "59") (name "/RXD_FTDI") (class "Default")
      (node (ref "R19") (pin "2") (pinfunction "2_2") (pintype "passive"))
      (node (ref "U2") (pin "1") (pinfunction "RXD_1") (pintype "passive"))
    )
    (net (code "60") (name "/TXD_FTDI") (class "Default")
      (node (ref "R20") (pin "2") (pinfunction "2_2") (pintype "passive"))
      (node (ref "U2") (pin "17") (pinfunction "TXD_17") (pintype "passive"))
    )
    (net (code "61") (name "/U0RXD") (class "Default")
      (node (ref "J2") (pin "6") (pinfunction "6_6") (pintype "passive"))
      (node (ref "R20") (pin "1") (pinfunction "1_1") (pintype "passive"))
      (node (ref "U1") (pin "40") (pinfunction "U0RXD/GPIO44/CLK_OUT2_40") (pintype "passive"))
    )
    (net (code "62") (name "/U0TXD") (class "Default")
      (node (ref "J2") (pin "7") (pinfunction "7_7") (pintype "passive"))
      (node (ref "R19") (pin "1") (pinfunction "1_1") (pintype "passive"))
      (node (ref "U1") (pin "39") (pinfunction "U0TXD/GPIO43/CLK_OUT1_39") (pintype "passive"))
    )
    (net (code "63") (name "/VBUS_SENSE") (class "Default")
      (node (ref "R10") (pin "1") (pinfunction "1_1") (pintype "passive"))
      (node (ref "R13") (pin "1") (pinfunction "1_1") (pintype "passive"))
      (node (ref "U2") (pin "16") (pinfunction "CBUS3_16") (pintype "passive"))
    )
    (net (code "64") (name "GND") (class "Default")
      (node (ref "C1") (pin "1") (pinfunction "1_1") (pintype "passive"))
      (node (ref "C10") (pin "1") (pinfunction "1_1") (pintype "passive"))
      (node (ref "C11") (pin "1") (pinfunction "1_1") (pintype "passive"))
      (node (ref "C12") (pin "1") (pinfunction "1_1") (pintype "passive"))
      (node (ref "C13") (pin "1") (pinfunction "1_1") (pintype "passive"))
      (node (ref "C14") (pin "1") (pinfunction "1_1") (pintype "passive"))
      (node (ref "C15") (pin "1") (pinfunction "1_1") (pintype "passive"))
      (node (ref "C16") (pin "1") (pinfunction "1_1") (pintype "passive"))
      (node (ref "C17") (pin "1") (pinfunction "1_1") (pintype "passive"))
      (node (ref "C2") (pin "1") (pinfunction "1_1") (pintype "passive"))
      (node (ref "C3") (pin "1") (pinfunction "1_1") (pintype "passive"))
      (node (ref "C4") (pin "1") (pinfunction "1_1") (pintype "passive"))
      (node (ref "C5") (pin "1") (pinfunction "1_1") (pintype "passive"))
      (node (ref "C6") (pin "1") (pinfunction "1_1") (pintype "passive"))
      (node (ref "C7") (pin "1") (pinfunction "1_1") (pintype "passive"))
      (node (ref "C8") (pin "1") (pinfunction "1_1") (pintype "passive"))
      (node (ref "C9") (pin "1") (pinfunction "1_1") (pintype "passive"))
      (node (ref "D1") (pin "1") (pinfunction "1_1") (pintype "passive"))
      (node (ref "D3") (pin "1") (pinfunction "1_1") (pintype "passive"))
      (node (ref "D4") (pin "1") (pinfunction "1_1") (pintype "passive"))
      (node (ref "D5") (pin "1") (pinfunction "1_1") (pintype "passive"))
      (node (ref "D6") (pin "1") (pinfunction "1_1") (pintype "passive"))
      (node (ref "D7") (pin "1") (pinfunction "1_1") (pintype "passive"))
      (node (ref "D8") (pin "1") (pinfunction "1_1") (pintype "passive"))
      (node (ref "J1") (pin "1") (pinfunction "1_1") (pintype "passive"))
      (node (ref "J1") (pin "23") (pinfunction "23_23") (pintype "passive"))
      (node (ref "J2") (pin "2") (pinfunction "2_2") (pintype "passive"))
      (node (ref "J2") (pin "24") (pinfunction "24_24") (pintype "passive"))
      (node (ref "J3") (pin "A1B12") (pinfunction "GND_A1B12_A1B12") (pintype "passive"))
      (node (ref "J3") (pin "B1A12") (pinfunction "GND_B1A12_B1A12") (pintype "passive"))
      (node (ref "J3") (pin "S1") (pinfunction "SHIELD_1_S1") (pintype "passive"))
      (node (ref "J3") (pin "S2") (pinfunction "SHIELD_2_S2") (pintype "passive"))
      (node (ref "J3") (pin "S3") (pinfunction "SHIELD_3_S3") (pintype "passive"))
      (node (ref "J3") (pin "S4") (pinfunction "SHIELD_4_S4") (pintype "passive"))
      (node (ref "J4") (pin "A1B12") (pinfunction "GND_A1B12_A1B12") (pintype "passive"))
      (node (ref "J4") (pin "B1A12") (pinfunction "GND_B1A12_B1A12") (pintype "passive"))
      (node (ref "J4") (pin "S1") (pinfunction "SHIELD_1_S1") (pintype "passive"))
      (node (ref "J4") (pin "S2") (pinfunction "SHIELD_2_S2") (pintype "passive"))
      (node (ref "J4") (pin "S3") (pinfunction "SHIELD_3_S3") (pintype "passive"))
      (node (ref "J4") (pin "S4") (pinfunction "SHIELD_4_S4") (pintype "passive"))
      (node (ref "R11") (pin "1") (pinfunction "1_1") (pintype "passive"))
      (node (ref "R12") (pin "1") (pinfunction "1_1") (pintype "passive"))
      (node (ref "R13") (pin "2") (pinfunction "2_2") (pintype "passive"))
      (node (ref "R14") (pin "1") (pinfunction "1_1") (pintype "passive"))
      (node (ref "R15") (pin "1") (pinfunction "1_1") (pintype "passive"))
      (node (ref "R9") (pin "2") (pinfunction "2_2") (pintype "passive"))
      (node (ref "SW1") (pin "3") (pinfunction "3_3") (pintype "passive"))
      (node (ref "SW1") (pin "4") (pinfunction "4_4") (pintype "passive"))
      (node (ref "SW2") (pin "3") (pinfunction "3_3") (pintype "passive"))
      (node (ref "SW2") (pin "4") (pinfunction "4_4") (pintype "passive"))
      (node (ref "U1") (pin "1") (pinfunction "GND_01_1") (pintype "passive"))
      (node (ref "U1") (pin "2") (pinfunction "GND_02_2") (pintype "passive"))
      (node (ref "U1") (pin "42") (pinfunction "GND_42") (pintype "passive"))
      (node (ref "U1") (pin "43") (pinfunction "GND_43") (pintype "passive"))
      (node (ref "U1") (pin "46") (pinfunction "GND_46_46") (pintype "passive"))
      (node (ref "U1") (pin "47") (pinfunction "GND_47_47") (pintype "passive"))
      (node (ref "U1") (pin "48") (pinfunction "GND_48_48") (pintype "passive"))
      (node (ref "U1") (pin "49") (pinfunction "GND_49_49") (pintype "passive"))
      (node (ref "U1") (pin "50") (pinfunction "GND_50_50") (pintype "passive"))
      (node (ref "U1") (pin "51") (pinfunction "GND_51_51") (pintype "passive"))
      (node (ref "U1") (pin "52") (pinfunction "GND_52_52") (pintype "passive"))
      (node (ref "U1") (pin "53") (pinfunction "GND_53_53") (pintype "passive"))
      (node (ref "U1") (pin "54") (pinfunction "GND_54_54") (pintype "passive"))
      (node (ref "U1") (pin "55") (pinfunction "GND_55_55") (pintype "passive"))
      (node (ref "U1") (pin "56") (pinfunction "GND_56_56") (pintype "passive"))
      (node (ref "U1") (pin "57") (pinfunction "GND_57_57") (pintype "passive"))
      (node (ref "U1") (pin "58") (pinfunction "GND_58_58") (pintype "passive"))
      (node (ref "U1") (pin "59") (pinfunction "GND_59_59") (pintype "passive"))
      (node (ref "U1") (pin "60") (pinfunction "GND_60_60") (pintype "passive"))
      (node (ref "U1") (pin "61") (pinfunction "GND_61_61") (pintype "passive"))
      (node (ref "U1") (pin "62") (pinfunction "GND_62_62") (pintype "passive"))
      (node (ref "U1") (pin "63") (pinfunction "GND_63_63") (pintype "passive"))
      (node (ref "U1") (pin "64") (pinfunction "GND_64_64") (pintype "passive"))
      (node (ref "U1") (pin "65") (pinfunction "GND_65_65") (pintype "passive"))
      (node (ref "U1") (pin "66") (pinfunction "GND_66_66") (pintype "passive"))
      (node (ref "U1") (pin "67") (pinfunction "GND_67_67") (pintype "passive"))
      (node (ref "U1") (pin "68") (pinfunction "GND_68_68") (pintype "passive"))
      (node (ref "U1") (pin "69") (pinfunction "GND_69_69") (pintype "passive"))
      (node (ref "U1") (pin "70") (pinfunction "GND_70_70") (pintype "passive"))
      (node (ref "U1") (pin "71") (pinfunction "GND_71_71") (pintype "passive"))
      (node (ref "U1") (pin "72") (pinfunction "GND_72_72") (pintype "passive"))
      (node (ref "U1") (pin "73") (pinfunction "GND_73_73") (pintype "passive"))
      (node (ref "U2") (pin "13") (pinfunction "GND_13") (pintype "passive"))
      (node (ref "U2") (pin "21") (pinfunction "GND_21") (pintype "passive"))
      (node (ref "U2") (pin "3") (pinfunction "GND_3") (pintype "passive"))
      (node (ref "U3") (pin "2") (pinfunction "GND_2") (pintype "power_in"))
      (node (ref "U3") (pin "4") (pinfunction "GND_4") (pintype "power_in"))
    )
    (net (code "65") (name "Net-(D1-Pad2)") (class "Default")
      (node (ref "D1") (pin "2") (pinfunction "2_2") (pintype "passive"))
      (node (ref "R3") (pin "1") (pinfunction "1_1") (pintype "passive"))
    )
    (net (code "66") (name "Net-(D2-Pad2)") (class "Default")
      (node (ref "D2") (pin "2") (pinfunction "2_2") (pintype "passive"))
      (node (ref "R4") (pin "1") (pinfunction "1_1") (pintype "passive"))
    )
    (net (code "67") (name "Net-(J3-CC1)") (class "Default")
      (node (ref "J3") (pin "A5") (pinfunction "CC1_A5") (pintype "passive"))
      (node (ref "R12") (pin "2") (pinfunction "2_2") (pintype "passive"))
    )
    (net (code "68") (name "Net-(J3-CC2)") (class "Default")
      (node (ref "J3") (pin "B5") (pinfunction "CC2_B5") (pintype "passive"))
      (node (ref "R11") (pin "2") (pinfunction "2_2") (pintype "passive"))
    )
    (net (code "69") (name "Net-(J4-CC1)") (class "Default")
      (node (ref "J4") (pin "A5") (pinfunction "CC1_A5") (pintype "passive"))
      (node (ref "R15") (pin "2") (pinfunction "2_2") (pintype "passive"))
    )
    (net (code "70") (name "Net-(J4-CC2)") (class "Default")
      (node (ref "J4") (pin "B5") (pinfunction "CC2_B5") (pintype "passive"))
      (node (ref "R14") (pin "2") (pinfunction "2_2") (pintype "passive"))
    )
    (net (code "71") (name "Net-(Q1-B)") (class "Default")
      (node (ref "Q1") (pin "1") (pinfunction "B_1") (pintype "passive"))
      (node (ref "R16") (pin "2") (pinfunction "2_2") (pintype "passive"))
    )
    (net (code "72") (name "Net-(Q2-B)") (class "Default")
      (node (ref "Q2") (pin "1") (pinfunction "B_1") (pintype "passive"))
      (node (ref "R18") (pin "2") (pinfunction "2_2") (pintype "passive"))
    )
    (net (code "73") (name "Net-(U2-CBUS0)") (class "Default")
      (node (ref "R9") (pin "1") (pinfunction "1_1") (pintype "passive"))
      (node (ref "U2") (pin "15") (pinfunction "CBUS0_15") (pintype "passive"))
    )
    (net (code "74") (name "unconnected-(J1-Pad24)") (class "Default")
      (node (ref "J1") (pin "24") (pinfunction "24_24") (pintype "passive+no_connect"))
    )
    (net (code "75") (name "unconnected-(J3-SBU1-PadA8)") (class "Default")
      (node (ref "J3") (pin "A8") (pinfunction "SBU1_A8") (pintype "passive+no_connect"))
    )
    (net (code "76") (name "unconnected-(J3-SBU2-PadB8)") (class "Default")
      (node (ref "J3") (pin "B8") (pinfunction "SBU2_B8") (pintype "passive+no_connect"))
    )
    (net (code "77") (name "unconnected-(J4-SBU1-PadA8)") (class "Default")
      (node (ref "J4") (pin "A8") (pinfunction "SBU1_A8") (pintype "passive+no_connect"))
    )
    (net (code "78") (name "unconnected-(J4-SBU2-PadB8)") (class "Default")
      (node (ref "J4") (pin "B8") (pinfunction "SBU2_B8") (pintype "passive+no_connect"))
    )
    (net (code "79") (name "unconnected-(U2-CBUS1-Pad14)") (class "Default")
      (node (ref "U2") (pin "14") (pinfunction "CBUS1_14") (pintype "passive+no_connect"))
    )
    (net (code "80") (name "unconnected-(U2-CBUS2-Pad7)") (class "Default")
      (node (ref "U2") (pin "7") (pinfunction "CBUS2_7") (pintype "passive+no_connect"))
    )
    (net (code "81") (name "unconnected-(U2-~{CTS}-Pad6)") (class "Default")
      (node (ref "U2") (pin "6") (pinfunction "~{CTS}_6") (pintype "passive+no_connect"))
    )
    (net (code "82") (name "unconnected-(U2-~{DCD}-Pad5)") (class "Default")
      (node (ref "U2") (pin "5") (pinfunction "~{DCD}_5") (pintype "passive+no_connect"))
    )
    (net (code "83") (name "unconnected-(U2-~{DSR}-Pad4)") (class "Default")
      (node (ref "U2") (pin "4") (pinfunction "~{DSR}_4") (pintype "passive+no_connect"))
    )
    (net (code "84") (name "unconnected-(U2-~{RI}-Pad2)") (class "Default")
      (node (ref "U2") (pin "2") (pinfunction "~{RI}_2") (pintype "passive+no_connect"))
    )
  )
)
